# BPW5031_Arcade_MegaWing.net
KiCad netlist of a schematic drawn in EAGLE
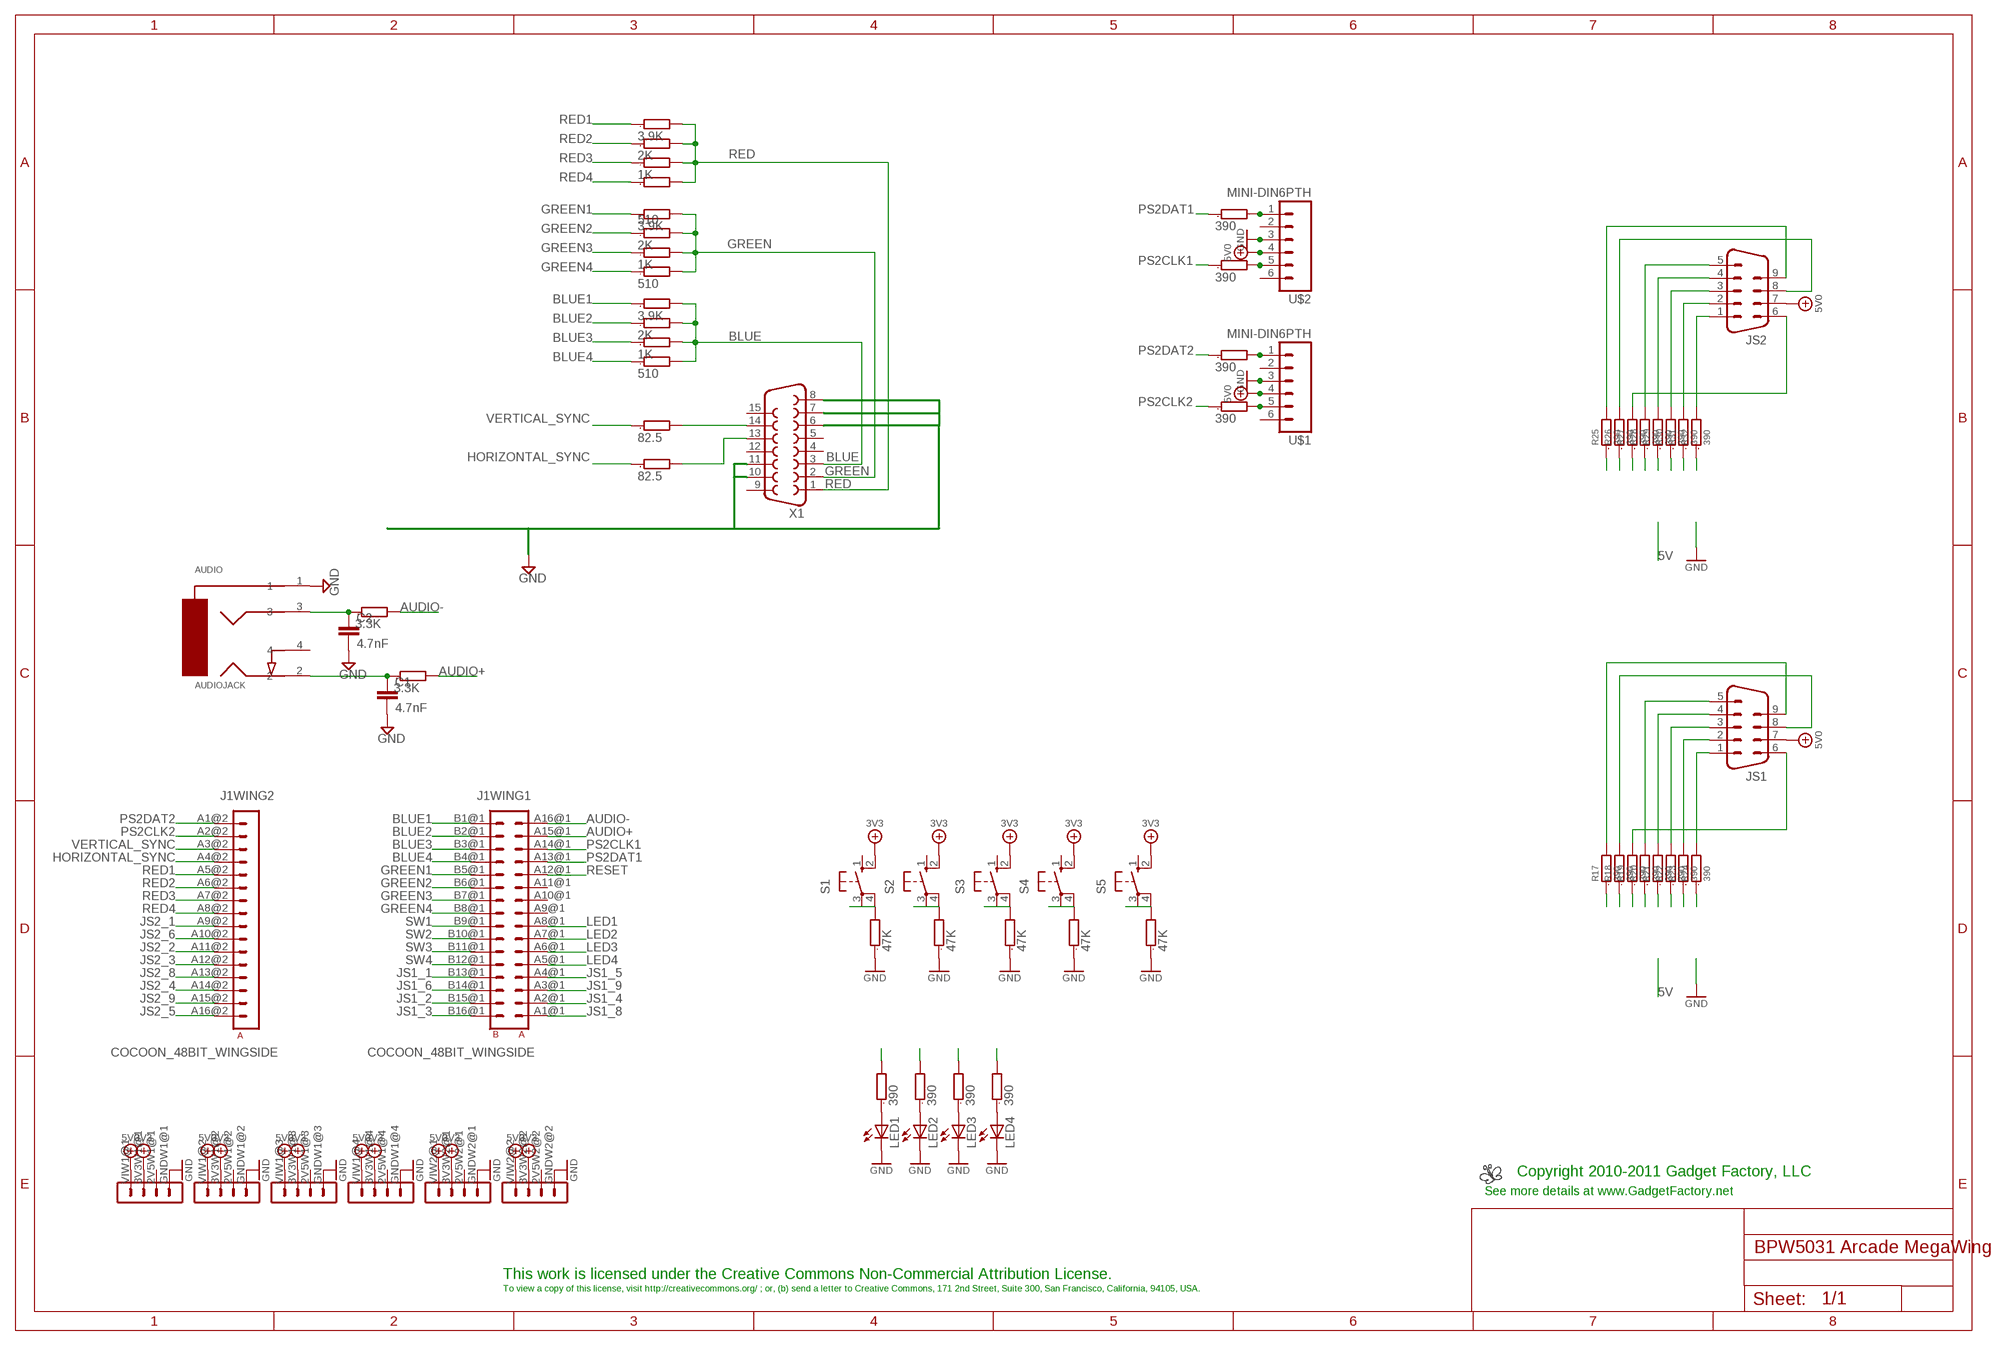
[diagram p0: schematic, sheet 1]

(export (version "E")
  (design (tool "Eeschema 10.0.6"))
  (components
    (comp (ref "AUDIO")
      (value "AUDIOJACK")
      (footprint "eagle-import:AUDJCK")
      (libsource (lib "eagle-import") (part "AUDIOJACK"))
    )
    (comp (ref "C1")
      (value "4.7nF")
      (footprint "eagle-import:C050-025X075")
      (libsource (lib "eagle-import") (part "C-EU050-025X075"))
    )
    (comp (ref "C2")
      (value "4.7nF")
      (footprint "eagle-import:C050-025X075")
      (libsource (lib "eagle-import") (part "C-EU050-025X075"))
    )
    (comp (ref "J1")
      (value "COCOON_48BIT_WINGSIDE")
      (footprint "eagle-import:COCOON_48BIT_WINGSIDE")
      (libsource (lib "eagle-import") (part "COCOON_48BIT_WINGSIDE"))
    )
    (comp (ref "JS1")
      (value "M09HP")
      (footprint "eagle-import:M09HP")
      (libsource (lib "eagle-import") (part "M09HP"))
    )
    (comp (ref "JS2")
      (value "M09HP")
      (footprint "eagle-import:M09HP")
      (libsource (lib "eagle-import") (part "M09HP"))
    )
    (comp (ref "LED1")
      (value "LEDCHIPLED_0603")
      (footprint "eagle-import:CHIPLED_0603")
      (libsource (lib "eagle-import") (part "LEDCHIPLED_0603"))
    )
    (comp (ref "LED2")
      (value "LEDCHIPLED_0603")
      (footprint "eagle-import:CHIPLED_0603")
      (libsource (lib "eagle-import") (part "LEDCHIPLED_0603"))
    )
    (comp (ref "LED3")
      (value "LEDCHIPLED_0603")
      (footprint "eagle-import:CHIPLED_0603")
      (libsource (lib "eagle-import") (part "LEDCHIPLED_0603"))
    )
    (comp (ref "LED4")
      (value "LEDCHIPLED_0603")
      (footprint "eagle-import:CHIPLED_0603")
      (libsource (lib "eagle-import") (part "LEDCHIPLED_0603"))
    )
    (comp (ref "LOGO2")
      (value "BUTTERFLY_LOGO")
      (footprint "eagle-import:BUTTERFLY_LOGO")
      (libsource (lib "eagle-import") (part "BUTTERFLY_LOGO"))
    )
    (comp (ref "R1")
      (value "3.9K")
      (footprint "eagle-import:0603")
      (libsource (lib "eagle-import") (part "R0603"))
    )
    (comp (ref "R2")
      (value "3.9K")
      (footprint "eagle-import:0603")
      (libsource (lib "eagle-import") (part "R0603"))
    )
    (comp (ref "R3")
      (value "3.9K")
      (footprint "eagle-import:0603")
      (libsource (lib "eagle-import") (part "R0603"))
    )
    (comp (ref "R4")
      (value "82.5")
      (footprint "eagle-import:0603")
      (libsource (lib "eagle-import") (part "R0603"))
    )
    (comp (ref "R5")
      (value "82.5")
      (footprint "eagle-import:0603")
      (libsource (lib "eagle-import") (part "R0603"))
    )
    (comp (ref "R6")
      (value "2K")
      (footprint "eagle-import:0603")
      (libsource (lib "eagle-import") (part "R0603"))
    )
    (comp (ref "R7")
      (value "2K")
      (footprint "eagle-import:0603")
      (libsource (lib "eagle-import") (part "R0603"))
    )
    (comp (ref "R8")
      (value "2K")
      (footprint "eagle-import:0603")
      (libsource (lib "eagle-import") (part "R0603"))
    )
    (comp (ref "R9")
      (value "1K")
      (footprint "eagle-import:0603")
      (libsource (lib "eagle-import") (part "R0603"))
    )
    (comp (ref "R10")
      (value "510")
      (footprint "eagle-import:0603")
      (libsource (lib "eagle-import") (part "R0603"))
    )
    (comp (ref "R11")
      (value "1K")
      (footprint "eagle-import:0603")
      (libsource (lib "eagle-import") (part "R0603"))
    )
    (comp (ref "R12")
      (value "510")
      (footprint "eagle-import:0603")
      (libsource (lib "eagle-import") (part "R0603"))
    )
    (comp (ref "R13")
      (value "1K")
      (footprint "eagle-import:0603")
      (libsource (lib "eagle-import") (part "R0603"))
    )
    (comp (ref "R14")
      (value "510")
      (footprint "eagle-import:0603")
      (libsource (lib "eagle-import") (part "R0603"))
    )
    (comp (ref "R15")
      (value "3.3K")
      (footprint "eagle-import:0603")
      (libsource (lib "eagle-import") (part "R0603"))
    )
    (comp (ref "R16")
      (value "3.3K")
      (footprint "eagle-import:0603")
      (libsource (lib "eagle-import") (part "R0603"))
    )
    (comp (ref "R17")
      (value "390")
      (footprint "eagle-import:0603")
      (libsource (lib "eagle-import") (part "R0603"))
    )
    (comp (ref "R18")
      (value "390")
      (footprint "eagle-import:0603")
      (libsource (lib "eagle-import") (part "R0603"))
    )
    (comp (ref "R19")
      (value "390")
      (footprint "eagle-import:0603")
      (libsource (lib "eagle-import") (part "R0603"))
    )
    (comp (ref "R20")
      (value "390")
      (footprint "eagle-import:0603")
      (libsource (lib "eagle-import") (part "R0603"))
    )
    (comp (ref "R21")
      (value "390")
      (footprint "eagle-import:0603")
      (libsource (lib "eagle-import") (part "R0603"))
    )
    (comp (ref "R22")
      (value "390")
      (footprint "eagle-import:0603")
      (libsource (lib "eagle-import") (part "R0603"))
    )
    (comp (ref "R23")
      (value "390")
      (footprint "eagle-import:0603")
      (libsource (lib "eagle-import") (part "R0603"))
    )
    (comp (ref "R24")
      (value "390")
      (footprint "eagle-import:0603")
      (libsource (lib "eagle-import") (part "R0603"))
    )
    (comp (ref "R25")
      (value "390")
      (footprint "eagle-import:0603")
      (libsource (lib "eagle-import") (part "R0603"))
    )
    (comp (ref "R26")
      (value "390")
      (footprint "eagle-import:0603")
      (libsource (lib "eagle-import") (part "R0603"))
    )
    (comp (ref "R27")
      (value "390")
      (footprint "eagle-import:0603")
      (libsource (lib "eagle-import") (part "R0603"))
    )
    (comp (ref "R28")
      (value "390")
      (footprint "eagle-import:0603")
      (libsource (lib "eagle-import") (part "R0603"))
    )
    (comp (ref "R29")
      (value "390")
      (footprint "eagle-import:0603")
      (libsource (lib "eagle-import") (part "R0603"))
    )
    (comp (ref "R30")
      (value "390")
      (footprint "eagle-import:0603")
      (libsource (lib "eagle-import") (part "R0603"))
    )
    (comp (ref "R31")
      (value "390")
      (footprint "eagle-import:0603")
      (libsource (lib "eagle-import") (part "R0603"))
    )
    (comp (ref "R32")
      (value "390")
      (footprint "eagle-import:0603")
      (libsource (lib "eagle-import") (part "R0603"))
    )
    (comp (ref "R33")
      (value "47K")
      (footprint "eagle-import:0603")
      (libsource (lib "eagle-import") (part "R0603"))
    )
    (comp (ref "R34")
      (value "47K")
      (footprint "eagle-import:0603")
      (libsource (lib "eagle-import") (part "R0603"))
    )
    (comp (ref "R35")
      (value "47K")
      (footprint "eagle-import:0603")
      (libsource (lib "eagle-import") (part "R0603"))
    )
    (comp (ref "R36")
      (value "47K")
      (footprint "eagle-import:0603")
      (libsource (lib "eagle-import") (part "R0603"))
    )
    (comp (ref "R37")
      (value "390")
      (footprint "eagle-import:0603")
      (libsource (lib "eagle-import") (part "R0603"))
    )
    (comp (ref "R38")
      (value "390")
      (footprint "eagle-import:0603")
      (libsource (lib "eagle-import") (part "R0603"))
    )
    (comp (ref "R39")
      (value "390")
      (footprint "eagle-import:0603")
      (libsource (lib "eagle-import") (part "R0603"))
    )
    (comp (ref "R40")
      (value "390")
      (footprint "eagle-import:0603")
      (libsource (lib "eagle-import") (part "R0603"))
    )
    (comp (ref "R41")
      (value "47K")
      (footprint "eagle-import:0603")
      (libsource (lib "eagle-import") (part "R0603"))
    )
    (comp (ref "R42")
      (value "390")
      (footprint "eagle-import:0603")
      (libsource (lib "eagle-import") (part "R0603"))
    )
    (comp (ref "R43")
      (value "390")
      (footprint "eagle-import:0603")
      (libsource (lib "eagle-import") (part "R0603"))
    )
    (comp (ref "R44")
      (value "390")
      (footprint "eagle-import:0603")
      (libsource (lib "eagle-import") (part "R0603"))
    )
    (comp (ref "R45")
      (value "390")
      (footprint "eagle-import:0603")
      (libsource (lib "eagle-import") (part "R0603"))
    )
    (comp (ref "S1")
      (value "10-XX")
      (footprint "eagle-import:B3F-10XX")
      (libsource (lib "eagle-import") (part "10-XX"))
    )
    (comp (ref "S2")
      (value "10-XX")
      (footprint "eagle-import:B3F-10XX")
      (libsource (lib "eagle-import") (part "10-XX"))
    )
    (comp (ref "S3")
      (value "10-XX")
      (footprint "eagle-import:B3F-10XX")
      (libsource (lib "eagle-import") (part "10-XX"))
    )
    (comp (ref "S4")
      (value "10-XX")
      (footprint "eagle-import:B3F-10XX")
      (libsource (lib "eagle-import") (part "10-XX"))
    )
    (comp (ref "S5")
      (value "10-XX")
      (footprint "eagle-import:B3F-10XX")
      (libsource (lib "eagle-import") (part "10-XX"))
    )
    (comp (ref "U$1")
      (value "MINI-DIN6PTH")
      (footprint "eagle-import:MINI-DIN6")
      (libsource (lib "eagle-import") (part "MINI-DIN6PTH"))
    )
    (comp (ref "U$2")
      (value "MINI-DIN6PTH")
      (footprint "eagle-import:MINI-DIN6")
      (libsource (lib "eagle-import") (part "MINI-DIN6PTH"))
    )
    (comp (ref "X1")
      (value "F15HDH")
      (footprint "eagle-import:HDF15H")
      (libsource (lib "eagle-import") (part "F15HDH"))
    )
  )
  (nets
    (net (code "2") (name "/AUDIO+") (class "Default")
      (node (ref "J1") (pin "A15@1") (pinfunction "A15_A15@1") (pintype "passive"))
      (node (ref "R16") (pin "2") (pinfunction "2_2") (pintype "passive"))
    )
    (net (code "3") (name "/AUDIO-") (class "Default")
      (node (ref "J1") (pin "A16@1") (pinfunction "A16_A16@1") (pintype "passive"))
      (node (ref "R15") (pin "2") (pinfunction "2_2") (pintype "passive"))
    )
    (net (code "4") (name "/BLUE") (class "Default")
      (node (ref "R13") (pin "2") (pinfunction "2_2") (pintype "passive"))
      (node (ref "R14") (pin "2") (pinfunction "2_2") (pintype "passive"))
      (node (ref "R3") (pin "2") (pinfunction "2_2") (pintype "passive"))
      (node (ref "R8") (pin "2") (pinfunction "2_2") (pintype "passive"))
      (node (ref "X1") (pin "3") (pinfunction "3_3") (pintype "passive"))
    )
    (net (code "5") (name "/BLUE1") (class "Default")
      (node (ref "J1") (pin "B1@1") (pinfunction "B1_B1@1") (pintype "passive"))
      (node (ref "R3") (pin "1") (pinfunction "1_1") (pintype "passive"))
    )
    (net (code "6") (name "/BLUE2") (class "Default")
      (node (ref "J1") (pin "B2@1") (pinfunction "B2_B2@1") (pintype "passive"))
      (node (ref "R8") (pin "1") (pinfunction "1_1") (pintype "passive"))
    )
    (net (code "7") (name "/BLUE3") (class "Default")
      (node (ref "J1") (pin "B3@1") (pinfunction "B3_B3@1") (pintype "passive"))
      (node (ref "R13") (pin "1") (pinfunction "1_1") (pintype "passive"))
    )
    (net (code "8") (name "/BLUE4") (class "Default")
      (node (ref "J1") (pin "B4@1") (pinfunction "B4_B4@1") (pintype "passive"))
      (node (ref "R14") (pin "1") (pinfunction "1_1") (pintype "passive"))
    )
    (net (code "9") (name "/GREEN") (class "Default")
      (node (ref "R11") (pin "2") (pinfunction "2_2") (pintype "passive"))
      (node (ref "R12") (pin "2") (pinfunction "2_2") (pintype "passive"))
      (node (ref "R2") (pin "2") (pinfunction "2_2") (pintype "passive"))
      (node (ref "R7") (pin "2") (pinfunction "2_2") (pintype "passive"))
      (node (ref "X1") (pin "2") (pinfunction "2_2") (pintype "passive"))
    )
    (net (code "10") (name "/GREEN1") (class "Default")
      (node (ref "J1") (pin "B5@1") (pinfunction "B5_B5@1") (pintype "passive"))
      (node (ref "R2") (pin "1") (pinfunction "1_1") (pintype "passive"))
    )
    (net (code "11") (name "/GREEN2") (class "Default")
      (node (ref "J1") (pin "B6@1") (pinfunction "B6_B6@1") (pintype "passive"))
      (node (ref "R7") (pin "1") (pinfunction "1_1") (pintype "passive"))
    )
    (net (code "12") (name "/GREEN3") (class "Default")
      (node (ref "J1") (pin "B7@1") (pinfunction "B7_B7@1") (pintype "passive"))
      (node (ref "R11") (pin "1") (pinfunction "1_1") (pintype "passive"))
    )
    (net (code "13") (name "/GREEN4") (class "Default")
      (node (ref "J1") (pin "B8@1") (pinfunction "B8_B8@1") (pintype "passive"))
      (node (ref "R12") (pin "1") (pinfunction "1_1") (pintype "passive"))
    )
    (net (code "14") (name "/HORIZONTAL_SYNC") (class "Default")
      (node (ref "J1") (pin "A4@2") (pinfunction "A4_A4@2") (pintype "passive"))
      (node (ref "R4") (pin "1") (pinfunction "1_1") (pintype "passive"))
    )
    (net (code "15") (name "/JS1_1") (class "Default")
      (node (ref "J1") (pin "B13@1") (pinfunction "B13_B13@1") (pintype "passive"))
      (node (ref "R32") (pin "1") (pinfunction "1_1") (pintype "passive"))
    )
    (net (code "16") (name "/JS1_2") (class "Default")
      (node (ref "J1") (pin "B15@1") (pinfunction "B15_B15@1") (pintype "passive"))
      (node (ref "R31") (pin "1") (pinfunction "1_1") (pintype "passive"))
    )
    (net (code "17") (name "/JS1_3") (class "Default")
      (node (ref "J1") (pin "B16@1") (pinfunction "B16_B16@1") (pintype "passive"))
      (node (ref "R30") (pin "1") (pinfunction "1_1") (pintype "passive"))
    )
    (net (code "18") (name "/JS1_4") (class "Default")
      (node (ref "J1") (pin "A2@1") (pinfunction "A2_A2@1") (pintype "passive"))
      (node (ref "R29") (pin "1") (pinfunction "1_1") (pintype "passive"))
    )
    (net (code "19") (name "/JS1_5") (class "Default")
      (node (ref "J1") (pin "A4@1") (pinfunction "A4_A4@1") (pintype "passive"))
      (node (ref "R28") (pin "1") (pinfunction "1_1") (pintype "passive"))
    )
    (net (code "20") (name "/JS1_6") (class "Default")
      (node (ref "J1") (pin "B14@1") (pinfunction "B14_B14@1") (pintype "passive"))
      (node (ref "R27") (pin "1") (pinfunction "1_1") (pintype "passive"))
    )
    (net (code "21") (name "/JS1_8") (class "Default")
      (node (ref "J1") (pin "A1@1") (pinfunction "A1_A1@1") (pintype "passive"))
      (node (ref "R26") (pin "1") (pinfunction "1_1") (pintype "passive"))
    )
    (net (code "22") (name "/JS1_9") (class "Default")
      (node (ref "J1") (pin "A3@1") (pinfunction "A3_A3@1") (pintype "passive"))
      (node (ref "R25") (pin "1") (pinfunction "1_1") (pintype "passive"))
    )
    (net (code "23") (name "/JS2_1") (class "Default")
      (node (ref "J1") (pin "A9@2") (pinfunction "A9_A9@2") (pintype "passive"))
      (node (ref "R24") (pin "1") (pinfunction "1_1") (pintype "passive"))
    )
    (net (code "24") (name "/JS2_2") (class "Default")
      (node (ref "J1") (pin "A11@2") (pinfunction "A11_A11@2") (pintype "passive"))
      (node (ref "R23") (pin "1") (pinfunction "1_1") (pintype "passive"))
    )
    (net (code "25") (name "/JS2_3") (class "Default")
      (node (ref "J1") (pin "A12@2") (pinfunction "A12_A12@2") (pintype "passive"))
      (node (ref "R22") (pin "1") (pinfunction "1_1") (pintype "passive"))
    )
    (net (code "26") (name "/JS2_4") (class "Default")
      (node (ref "J1") (pin "A14@2") (pinfunction "A14_A14@2") (pintype "passive"))
      (node (ref "R21") (pin "1") (pinfunction "1_1") (pintype "passive"))
    )
    (net (code "27") (name "/JS2_5") (class "Default")
      (node (ref "J1") (pin "A16@2") (pinfunction "A16_A16@2") (pintype "passive"))
      (node (ref "R20") (pin "1") (pinfunction "1_1") (pintype "passive"))
    )
    (net (code "28") (name "/JS2_6") (class "Default")
      (node (ref "J1") (pin "A10@2") (pinfunction "A10_A10@2") (pintype "passive"))
      (node (ref "R19") (pin "1") (pinfunction "1_1") (pintype "passive"))
    )
    (net (code "29") (name "/JS2_8") (class "Default")
      (node (ref "J1") (pin "A13@2") (pinfunction "A13_A13@2") (pintype "passive"))
      (node (ref "R18") (pin "1") (pinfunction "1_1") (pintype "passive"))
    )
    (net (code "30") (name "/JS2_9") (class "Default")
      (node (ref "J1") (pin "A15@2") (pinfunction "A15_A15@2") (pintype "passive"))
      (node (ref "R17") (pin "1") (pinfunction "1_1") (pintype "passive"))
    )
    (net (code "31") (name "/LED1") (class "Default")
      (node (ref "J1") (pin "A8@1") (pinfunction "A8_A8@1") (pintype "passive"))
      (node (ref "R37") (pin "2") (pinfunction "2_2") (pintype "passive"))
    )
    (net (code "32") (name "/LED2") (class "Default")
      (node (ref "J1") (pin "A7@1") (pinfunction "A7_A7@1") (pintype "passive"))
      (node (ref "R38") (pin "2") (pinfunction "2_2") (pintype "passive"))
    )
    (net (code "33") (name "/LED3") (class "Default")
      (node (ref "J1") (pin "A6@1") (pinfunction "A6_A6@1") (pintype "passive"))
      (node (ref "R39") (pin "2") (pinfunction "2_2") (pintype "passive"))
    )
    (net (code "34") (name "/LED4") (class "Default")
      (node (ref "J1") (pin "A5@1") (pinfunction "A5_A5@1") (pintype "passive"))
      (node (ref "R40") (pin "2") (pinfunction "2_2") (pintype "passive"))
    )
    (net (code "35") (name "/PS2CLK1") (class "Default")
      (node (ref "J1") (pin "A14@1") (pinfunction "A14_A14@1") (pintype "passive"))
      (node (ref "R43") (pin "1") (pinfunction "1_1") (pintype "passive"))
    )
    (net (code "36") (name "/PS2CLK2") (class "Default")
      (node (ref "J1") (pin "A2@2") (pinfunction "A2_A2@2") (pintype "passive"))
      (node (ref "R45") (pin "1") (pinfunction "1_1") (pintype "passive"))
    )
    (net (code "37") (name "/PS2DAT1") (class "Default")
      (node (ref "J1") (pin "A13@1") (pinfunction "A13_A13@1") (pintype "passive"))
      (node (ref "R42") (pin "1") (pinfunction "1_1") (pintype "passive"))
    )
    (net (code "38") (name "/PS2DAT2") (class "Default")
      (node (ref "J1") (pin "A1@2") (pinfunction "A1_A1@2") (pintype "passive"))
      (node (ref "R44") (pin "1") (pinfunction "1_1") (pintype "passive"))
    )
    (net (code "39") (name "/RED") (class "Default")
      (node (ref "R1") (pin "2") (pinfunction "2_2") (pintype "passive"))
      (node (ref "R10") (pin "2") (pinfunction "2_2") (pintype "passive"))
      (node (ref "R6") (pin "2") (pinfunction "2_2") (pintype "passive"))
      (node (ref "R9") (pin "2") (pinfunction "2_2") (pintype "passive"))
      (node (ref "X1") (pin "1") (pinfunction "1_1") (pintype "passive"))
    )
    (net (code "40") (name "/RED1") (class "Default")
      (node (ref "J1") (pin "A5@2") (pinfunction "A5_A5@2") (pintype "passive"))
      (node (ref "R1") (pin "1") (pinfunction "1_1") (pintype "passive"))
    )
    (net (code "41") (name "/RED2") (class "Default")
      (node (ref "J1") (pin "A6@2") (pinfunction "A6_A6@2") (pintype "passive"))
      (node (ref "R6") (pin "1") (pinfunction "1_1") (pintype "passive"))
    )
    (net (code "42") (name "/RED3") (class "Default")
      (node (ref "J1") (pin "A7@2") (pinfunction "A7_A7@2") (pintype "passive"))
      (node (ref "R9") (pin "1") (pinfunction "1_1") (pintype "passive"))
    )
    (net (code "43") (name "/RED4") (class "Default")
      (node (ref "J1") (pin "A8@2") (pinfunction "A8_A8@2") (pintype "passive"))
      (node (ref "R10") (pin "1") (pinfunction "1_1") (pintype "passive"))
    )
    (net (code "44") (name "/RESET") (class "Default")
      (node (ref "J1") (pin "A12@1") (pinfunction "A12_A12@1") (pintype "passive"))
      (node (ref "R41") (pin "2") (pinfunction "2_2") (pintype "passive"))
      (node (ref "S5") (pin "3") (pinfunction "P_3") (pintype "passive"))
      (node (ref "S5") (pin "4") (pinfunction "P1_4") (pintype "passive"))
    )
    (net (code "45") (name "/SW1") (class "Default")
      (node (ref "J1") (pin "B9@1") (pinfunction "B9_B9@1") (pintype "passive"))
      (node (ref "R33") (pin "2") (pinfunction "2_2") (pintype "passive"))
      (node (ref "S1") (pin "3") (pinfunction "P_3") (pintype "passive"))
      (node (ref "S1") (pin "4") (pinfunction "P1_4") (pintype "passive"))
    )
    (net (code "46") (name "/SW2") (class "Default")
      (node (ref "J1") (pin "B10@1") (pinfunction "B10_B10@1") (pintype "passive"))
      (node (ref "R34") (pin "2") (pinfunction "2_2") (pintype "passive"))
      (node (ref "S2") (pin "3") (pinfunction "P_3") (pintype "passive"))
      (node (ref "S2") (pin "4") (pinfunction "P1_4") (pintype "passive"))
    )
    (net (code "47") (name "/SW3") (class "Default")
      (node (ref "J1") (pin "B11@1") (pinfunction "B11_B11@1") (pintype "passive"))
      (node (ref "R35") (pin "2") (pinfunction "2_2") (pintype "passive"))
      (node (ref "S3") (pin "3") (pinfunction "P_3") (pintype "passive"))
      (node (ref "S3") (pin "4") (pinfunction "P1_4") (pintype "passive"))
    )
    (net (code "48") (name "/SW4") (class "Default")
      (node (ref "J1") (pin "B12@1") (pinfunction "B12_B12@1") (pintype "passive"))
      (node (ref "R36") (pin "2") (pinfunction "2_2") (pintype "passive"))
      (node (ref "S4") (pin "3") (pinfunction "P_3") (pintype "passive"))
      (node (ref "S4") (pin "4") (pinfunction "P1_4") (pintype "passive"))
    )
    (net (code "49") (name "/VERTICAL_SYNC") (class "Default")
      (node (ref "J1") (pin "A3@2") (pinfunction "A3_A3@2") (pintype "passive"))
      (node (ref "R5") (pin "1") (pinfunction "1_1") (pintype "passive"))
    )
    (net (code "50") (name "3V3") (class "Default")
      (node (ref "J1") (pin "3V3W1@1") (pinfunction "3V3_3V3W1@1") (pintype "passive"))
      (node (ref "J1") (pin "3V3W1@2") (pinfunction "3V3_3V3W1@2") (pintype "passive"))
      (node (ref "J1") (pin "3V3W1@3") (pinfunction "3V3_3V3W1@3") (pintype "passive"))
      (node (ref "J1") (pin "3V3W1@4") (pinfunction "3V3_3V3W1@4") (pintype "passive"))
      (node (ref "J1") (pin "3V3W2@1") (pinfunction "3V3_3V3W2@1") (pintype "passive"))
      (node (ref "J1") (pin "3V3W2@2") (pinfunction "3V3_3V3W2@2") (pintype "passive"))
      (node (ref "S1") (pin "2") (pinfunction "S1_2") (pintype "passive"))
      (node (ref "S2") (pin "2") (pinfunction "S1_2") (pintype "passive"))
      (node (ref "S3") (pin "2") (pinfunction "S1_2") (pintype "passive"))
      (node (ref "S4") (pin "2") (pinfunction "S1_2") (pintype "passive"))
      (node (ref "S5") (pin "2") (pinfunction "S1_2") (pintype "passive"))
    )
    (net (code "51") (name "5V0") (class "Default")
      (node (ref "J1") (pin "VIW1@1") (pinfunction "5V_VIW1@1") (pintype "passive"))
      (node (ref "J1") (pin "VIW1@2") (pinfunction "5V_VIW1@2") (pintype "passive"))
      (node (ref "J1") (pin "VIW1@3") (pinfunction "5V_VIW1@3") (pintype "passive"))
      (node (ref "J1") (pin "VIW1@4") (pinfunction "5V_VIW1@4") (pintype "passive"))
      (node (ref "J1") (pin "VIW2@1") (pinfunction "5V_VIW2@1") (pintype "passive"))
      (node (ref "J1") (pin "VIW2@2") (pinfunction "5V_VIW2@2") (pintype "passive"))
      (node (ref "JS1") (pin "7") (pinfunction "7_7") (pintype "passive"))
      (node (ref "JS2") (pin "7") (pinfunction "7_7") (pintype "passive"))
      (node (ref "U$1") (pin "4") (pinfunction "4_4") (pintype "passive"))
      (node (ref "U$2") (pin "4") (pinfunction "4_4") (pintype "passive"))
    )
    (net (code "52") (name "GND") (class "Default")
      (node (ref "AUDIO") (pin "1") (pinfunction "1_1") (pintype "bidirectional"))
      (node (ref "C1") (pin "2") (pinfunction "2_2") (pintype "passive"))
      (node (ref "C2") (pin "2") (pinfunction "2_2") (pintype "passive"))
      (node (ref "J1") (pin "GNDW1@1") (pinfunction "GND_GNDW1@1") (pintype "passive"))
      (node (ref "J1") (pin "GNDW1@2") (pinfunction "GND_GNDW1@2") (pintype "passive"))
      (node (ref "J1") (pin "GNDW1@3") (pinfunction "GND_GNDW1@3") (pintype "passive"))
      (node (ref "J1") (pin "GNDW1@4") (pinfunction "GND_GNDW1@4") (pintype "passive"))
      (node (ref "J1") (pin "GNDW2@1") (pinfunction "GND_GNDW2@1") (pintype "passive"))
      (node (ref "J1") (pin "GNDW2@2") (pinfunction "GND_GNDW2@2") (pintype "passive"))
      (node (ref "LED1") (pin "C") (pinfunction "C_C") (pintype "passive"))
      (node (ref "LED2") (pin "C") (pinfunction "C_C") (pintype "passive"))
      (node (ref "LED3") (pin "C") (pinfunction "C_C") (pintype "passive"))
      (node (ref "LED4") (pin "C") (pinfunction "C_C") (pintype "passive"))
      (node (ref "R33") (pin "1") (pinfunction "1_1") (pintype "passive"))
      (node (ref "R34") (pin "1") (pinfunction "1_1") (pintype "passive"))
      (node (ref "R35") (pin "1") (pinfunction "1_1") (pintype "passive"))
      (node (ref "R36") (pin "1") (pinfunction "1_1") (pintype "passive"))
      (node (ref "R41") (pin "1") (pinfunction "1_1") (pintype "passive"))
      (node (ref "U$1") (pin "3") (pinfunction "3_3") (pintype "passive"))
      (node (ref "U$2") (pin "3") (pinfunction "3_3") (pintype "passive"))
      (node (ref "X1") (pin "10") (pinfunction "10_10") (pintype "passive"))
      (node (ref "X1") (pin "11") (pinfunction "11_11") (pintype "passive"))
      (node (ref "X1") (pin "6") (pinfunction "6_6") (pintype "passive"))
      (node (ref "X1") (pin "7") (pinfunction "7_7") (pintype "passive"))
      (node (ref "X1") (pin "8") (pinfunction "8_8") (pintype "passive"))
    )
    (net (code "53") (name "Net-(AUDIO-Pad2)") (class "Default")
      (node (ref "AUDIO") (pin "2") (pinfunction "2_2") (pintype "bidirectional"))
      (node (ref "C1") (pin "1") (pinfunction "1_1") (pintype "passive"))
      (node (ref "R16") (pin "1") (pinfunction "1_1") (pintype "passive"))
    )
    (net (code "54") (name "Net-(AUDIO-Pad3)") (class "Default")
      (node (ref "AUDIO") (pin "3") (pinfunction "3_3") (pintype "bidirectional"))
      (node (ref "C2") (pin "1") (pinfunction "1_1") (pintype "passive"))
      (node (ref "R15") (pin "1") (pinfunction "1_1") (pintype "passive"))
    )
    (net (code "55") (name "Net-(JS1-Pad1)") (class "Default")
      (node (ref "JS1") (pin "1") (pinfunction "1_1") (pintype "passive"))
      (node (ref "R24") (pin "2") (pinfunction "2_2") (pintype "passive"))
    )
    (net (code "56") (name "Net-(JS1-Pad2)") (class "Default")
      (node (ref "JS1") (pin "2") (pinfunction "2_2") (pintype "passive"))
      (node (ref "R23") (pin "2") (pinfunction "2_2") (pintype "passive"))
    )
    (net (code "57") (name "Net-(JS1-Pad3)") (class "Default")
      (node (ref "JS1") (pin "3") (pinfunction "3_3") (pintype "passive"))
      (node (ref "R22") (pin "2") (pinfunction "2_2") (pintype "passive"))
    )
    (net (code "58") (name "Net-(JS1-Pad4)") (class "Default")
      (node (ref "JS1") (pin "4") (pinfunction "4_4") (pintype "passive"))
      (node (ref "R21") (pin "2") (pinfunction "2_2") (pintype "passive"))
    )
    (net (code "59") (name "Net-(JS1-Pad5)") (class "Default")
      (node (ref "JS1") (pin "5") (pinfunction "5_5") (pintype "passive"))
      (node (ref "R20") (pin "2") (pinfunction "2_2") (pintype "passive"))
    )
    (net (code "60") (name "Net-(JS1-Pad6)") (class "Default")
      (node (ref "JS1") (pin "6") (pinfunction "6_6") (pintype "passive"))
      (node (ref "R19") (pin "2") (pinfunction "2_2") (pintype "passive"))
    )
    (net (code "61") (name "Net-(JS1-Pad8)") (class "Default")
      (node (ref "JS1") (pin "8") (pinfunction "8_8") (pintype "passive"))
      (node (ref "R18") (pin "2") (pinfunction "2_2") (pintype "passive"))
    )
    (net (code "62") (name "Net-(JS1-Pad9)") (class "Default")
      (node (ref "JS1") (pin "9") (pinfunction "9_9") (pintype "passive"))
      (node (ref "R17") (pin "2") (pinfunction "2_2") (pintype "passive"))
    )
    (net (code "63") (name "Net-(JS2-Pad1)") (class "Default")
      (node (ref "JS2") (pin "1") (pinfunction "1_1") (pintype "passive"))
      (node (ref "R32") (pin "2") (pinfunction "2_2") (pintype "passive"))
    )
    (net (code "64") (name "Net-(JS2-Pad2)") (class "Default")
      (node (ref "JS2") (pin "2") (pinfunction "2_2") (pintype "passive"))
      (node (ref "R31") (pin "2") (pinfunction "2_2") (pintype "passive"))
    )
    (net (code "65") (name "Net-(JS2-Pad3)") (class "Default")
      (node (ref "JS2") (pin "3") (pinfunction "3_3") (pintype "passive"))
      (node (ref "R30") (pin "2") (pinfunction "2_2") (pintype "passive"))
    )
    (net (code "66") (name "Net-(JS2-Pad4)") (class "Default")
      (node (ref "JS2") (pin "4") (pinfunction "4_4") (pintype "passive"))
      (node (ref "R29") (pin "2") (pinfunction "2_2") (pintype "passive"))
    )
    (net (code "67") (name "Net-(JS2-Pad5)") (class "Default")
      (node (ref "JS2") (pin "5") (pinfunction "5_5") (pintype "passive"))
      (node (ref "R28") (pin "2") (pinfunction "2_2") (pintype "passive"))
    )
    (net (code "68") (name "Net-(JS2-Pad6)") (class "Default")
      (node (ref "JS2") (pin "6") (pinfunction "6_6") (pintype "passive"))
      (node (ref "R27") (pin "2") (pinfunction "2_2") (pintype "passive"))
    )
    (net (code "69") (name "Net-(JS2-Pad8)") (class "Default")
      (node (ref "JS2") (pin "8") (pinfunction "8_8") (pintype "passive"))
      (node (ref "R26") (pin "2") (pinfunction "2_2") (pintype "passive"))
    )
    (net (code "70") (name "Net-(JS2-Pad9)") (class "Default")
      (node (ref "JS2") (pin "9") (pinfunction "9_9") (pintype "passive"))
      (node (ref "R25") (pin "2") (pinfunction "2_2") (pintype "passive"))
    )
    (net (code "71") (name "Net-(LED1-PadA)") (class "Default")
      (node (ref "LED1") (pin "A") (pinfunction "A_A") (pintype "passive"))
      (node (ref "R37") (pin "1") (pinfunction "1_1") (pintype "passive"))
    )
    (net (code "72") (name "Net-(LED2-PadA)") (class "Default")
      (node (ref "LED2") (pin "A") (pinfunction "A_A") (pintype "passive"))
      (node (ref "R38") (pin "1") (pinfunction "1_1") (pintype "passive"))
    )
    (net (code "73") (name "Net-(LED3-PadA)") (class "Default")
      (node (ref "LED3") (pin "A") (pinfunction "A_A") (pintype "passive"))
      (node (ref "R39") (pin "1") (pinfunction "1_1") (pintype "passive"))
    )
    (net (code "74") (name "Net-(LED4-PadA)") (class "Default")
      (node (ref "LED4") (pin "A") (pinfunction "A_A") (pintype "passive"))
      (node (ref "R40") (pin "1") (pinfunction "1_1") (pintype "passive"))
    )
    (net (code "75") (name "Net-(R4-Pad2)") (class "Default")
      (node (ref "R4") (pin "2") (pinfunction "2_2") (pintype "passive"))
      (node (ref "X1") (pin "13") (pinfunction "13_13") (pintype "passive"))
    )
    (net (code "76") (name "Net-(R5-Pad2)") (class "Default")
      (node (ref "R5") (pin "2") (pinfunction "2_2") (pintype "passive"))
      (node (ref "X1") (pin "14") (pinfunction "14_14") (pintype "passive"))
    )
    (net (code "77") (name "Net-(R42-Pad2)") (class "Default")
      (node (ref "R42") (pin "2") (pinfunction "2_2") (pintype "passive"))
      (node (ref "U$2") (pin "1") (pinfunction "1_1") (pintype "passive"))
    )
    (net (code "78") (name "Net-(R43-Pad2)") (class "Default")
      (node (ref "R43") (pin "2") (pinfunction "2_2") (pintype "passive"))
      (node (ref "U$2") (pin "5") (pinfunction "5_5") (pintype "passive"))
    )
    (net (code "79") (name "Net-(R44-Pad2)") (class "Default")
      (node (ref "R44") (pin "2") (pinfunction "2_2") (pintype "passive"))
      (node (ref "U$1") (pin "1") (pinfunction "1_1") (pintype "passive"))
    )
    (net (code "80") (name "Net-(R45-Pad2)") (class "Default")
      (node (ref "R45") (pin "2") (pinfunction "2_2") (pintype "passive"))
      (node (ref "U$1") (pin "5") (pinfunction "5_5") (pintype "passive"))
    )
    (net (code "81") (name "unconnected-(AUDIO-Pad4)") (class "Default")
      (node (ref "AUDIO") (pin "4") (pinfunction "4_4") (pintype "bidirectional"))
    )
    (net (code "82") (name "unconnected-(J1A-2V5-Pad2V5W1@1)") (class "Default")
      (node (ref "J1") (pin "2V5W1@1") (pinfunction "2V5_2V5W1@1") (pintype "passive"))
    )
    (net (code "83") (name "unconnected-(J1B-2V5-Pad2V5W1@2)") (class "Default")
      (node (ref "J1") (pin "2V5W1@2") (pinfunction "2V5_2V5W1@2") (pintype "passive"))
    )
    (net (code "84") (name "unconnected-(J1C-2V5-Pad2V5W1@3)") (class "Default")
      (node (ref "J1") (pin "2V5W1@3") (pinfunction "2V5_2V5W1@3") (pintype "passive"))
    )
    (net (code "85") (name "unconnected-(J1D-2V5-Pad2V5W1@4)") (class "Default")
      (node (ref "J1") (pin "2V5W1@4") (pinfunction "2V5_2V5W1@4") (pintype "passive"))
    )
    (net (code "86") (name "unconnected-(J1E-2V5-Pad2V5W2@1)") (class "Default")
      (node (ref "J1") (pin "2V5W2@1") (pinfunction "2V5_2V5W2@1") (pintype "passive"))
    )
    (net (code "87") (name "unconnected-(J1F-2V5-Pad2V5W2@2)") (class "Default")
      (node (ref "J1") (pin "2V5W2@2") (pinfunction "2V5_2V5W2@2") (pintype "passive"))
    )
    (net (code "88") (name "unconnected-(J1G-A9-PadA9@1)") (class "Default")
      (node (ref "J1") (pin "A9@1") (pinfunction "A9_A9@1") (pintype "passive"))
    )
    (net (code "89") (name "unconnected-(J1G-A10-PadA10@1)") (class "Default")
      (node (ref "J1") (pin "A10@1") (pinfunction "A10_A10@1") (pintype "passive"))
    )
    (net (code "90") (name "unconnected-(J1G-A11-PadA11@1)") (class "Default")
      (node (ref "J1") (pin "A11@1") (pinfunction "A11_A11@1") (pintype "passive"))
    )
    (net (code "91") (name "unconnected-(S1-S-Pad1)") (class "Default")
      (node (ref "S1") (pin "1") (pinfunction "S_1") (pintype "passive"))
    )
    (net (code "92") (name "unconnected-(S2-S-Pad1)") (class "Default")
      (node (ref "S2") (pin "1") (pinfunction "S_1") (pintype "passive"))
    )
    (net (code "93") (name "unconnected-(S3-S-Pad1)") (class "Default")
      (node (ref "S3") (pin "1") (pinfunction "S_1") (pintype "passive"))
    )
    (net (code "94") (name "unconnected-(S4-S-Pad1)") (class "Default")
      (node (ref "S4") (pin "1") (pinfunction "S_1") (pintype "passive"))
    )
    (net (code "95") (name "unconnected-(S5-S-Pad1)") (class "Default")
      (node (ref "S5") (pin "1") (pinfunction "S_1") (pintype "passive"))
    )
    (net (code "96") (name "unconnected-(U$1-Pad2)") (class "Default")
      (node (ref "U$1") (pin "2") (pinfunction "2_2") (pintype "passive"))
    )
    (net (code "97") (name "unconnected-(U$1-Pad6)") (class "Default")
      (node (ref "U$1") (pin "6") (pinfunction "6_6") (pintype "passive"))
    )
    (net (code "98") (name "unconnected-(U$2-Pad2)") (class "Default")
      (node (ref "U$2") (pin "2") (pinfunction "2_2") (pintype "passive"))
    )
    (net (code "99") (name "unconnected-(U$2-Pad6)") (class "Default")
      (node (ref "U$2") (pin "6") (pinfunction "6_6") (pintype "passive"))
    )
    (net (code "100") (name "unconnected-(X1-Pad4)") (class "Default")
      (node (ref "X1") (pin "4") (pinfunction "4_4") (pintype "passive"))
    )
    (net (code "101") (name "unconnected-(X1-Pad5)") (class "Default")
      (node (ref "X1") (pin "5") (pinfunction "5_5") (pintype "passive"))
    )
    (net (code "102") (name "unconnected-(X1-Pad9)") (class "Default")
      (node (ref "X1") (pin "9") (pinfunction "9_9") (pintype "passive"))
    )
    (net (code "103") (name "unconnected-(X1-Pad12)") (class "Default")
      (node (ref "X1") (pin "12") (pinfunction "12_12") (pintype "passive"))
    )
    (net (code "104") (name "unconnected-(X1-Pad15)") (class "Default")
      (node (ref "X1") (pin "15") (pinfunction "15_15") (pintype "passive"))
    )
  )
)
